# reaction-game.net
KiCad netlist of a schematic drawn in EasyEDA
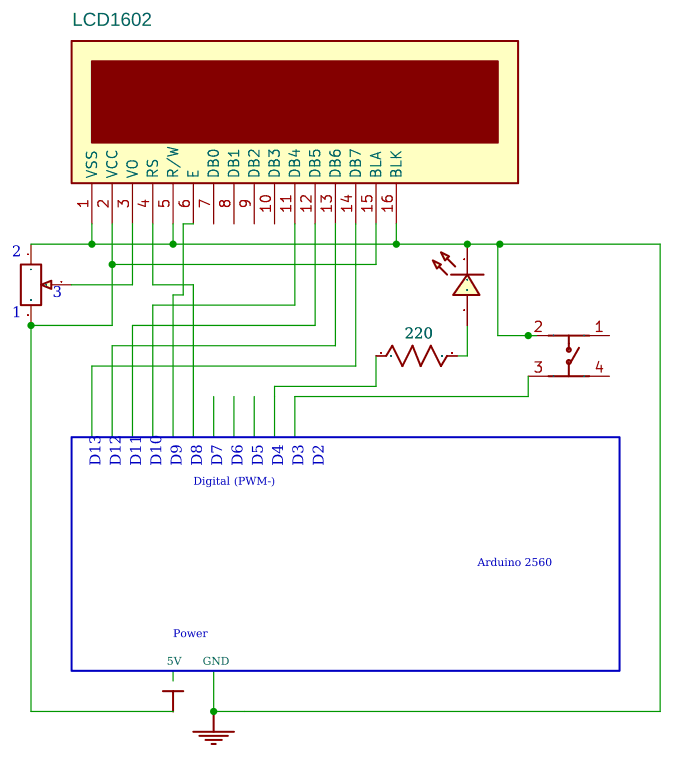
[diagram p0: schematic sheet]

(export (version "E")
  (design (tool "Eeschema 10.0.6"))
  (components
    (comp (ref "KEY1")
      (value "button6*6*8")
      (fields (field (name "BOM_Supplier Part") "C59982"))
      (libsource (lib "") (part "button6*6*8"))
    )
    (comp (ref "LCD1")
      (value "LCD1602")
      (fields
        (field (name "BOM_Manufacturer Part") "LCM1602K-NSW-BBW")
        (field (name "BOM_Supplier Part") "C83275")
      )
      (libsource (lib "") (part "LCD1602"))
    )
    (comp (ref "LED1")
      (value "LED-0603_R")
      (fields
        (field (name "BOM_Manufacturer Part") "19-217/R6C-AL1M2VY/3T")
        (field (name "BOM_Supplier Part") "C72044")
      )
      (libsource (lib "") (part "LED-0603_R"))
    )
    (comp (ref "R1") (value "220") (libsource (lib "") (part "R_0603_US")))
    (comp (ref "RP1") (value "R_3386P_EU") (libsource (lib "") (part "R_3386P_EU")))
  )
  (nets
    (net (code "1") (name "5V") (class "Default")
      (node (ref "LCD1") (pin "15") (pinfunction "BLA_15") (pintype "unspecified"))
      (node (ref "LCD1") (pin "2") (pinfunction "VCC_2") (pintype "unspecified"))
      (node (ref "RP1") (pin "3") (pinfunction "3_3") (pintype "input"))
    )
    (net (code "2") (name "GND") (class "Default")
      (node (ref "KEY1") (pin "2") (pinfunction "2_2") (pintype "unspecified"))
      (node (ref "LCD1") (pin "1") (pinfunction "VSS_1") (pintype "unspecified"))
      (node (ref "LCD1") (pin "16") (pinfunction "BLK_16") (pintype "unspecified"))
      (node (ref "LCD1") (pin "5") (pinfunction "R/W_5") (pintype "unspecified"))
      (node (ref "LED1") (pin "2") (pinfunction "2_2") (pintype "unspecified"))
      (node (ref "RP1") (pin "1") (pinfunction "1_1") (pintype "input"))
    )
    (net (code "3") (name "Net-(LCD1-VO)") (class "Default")
      (node (ref "LCD1") (pin "3") (pinfunction "VO_3") (pintype "unspecified"))
      (node (ref "RP1") (pin "2") (pinfunction "2_2") (pintype "input"))
    )
    (net (code "4") (name "Net-(LED1-Pad1)") (class "Default")
      (node (ref "LED1") (pin "1") (pinfunction "1_1") (pintype "unspecified"))
      (node (ref "R1") (pin "2") (pinfunction "2_2") (pintype "unspecified"))
    )
    (net (code "5") (name "unconnected-(KEY1-Pad1)") (class "Default")
      (node (ref "KEY1") (pin "1") (pinfunction "1_1") (pintype "unspecified"))
    )
    (net (code "6") (name "unconnected-(KEY1-Pad3)") (class "Default")
      (node (ref "KEY1") (pin "3") (pinfunction "3_3") (pintype "unspecified"))
    )
    (net (code "7") (name "unconnected-(KEY1-Pad4)") (class "Default")
      (node (ref "KEY1") (pin "4") (pinfunction "4_4") (pintype "unspecified"))
    )
    (net (code "8") (name "unconnected-(LCD1-DB0-Pad7)") (class "Default")
      (node (ref "LCD1") (pin "7") (pinfunction "DB0_7") (pintype "unspecified"))
    )
    (net (code "9") (name "unconnected-(LCD1-DB1-Pad8)") (class "Default")
      (node (ref "LCD1") (pin "8") (pinfunction "DB1_8") (pintype "unspecified"))
    )
    (net (code "10") (name "unconnected-(LCD1-DB2-Pad9)") (class "Default")
      (node (ref "LCD1") (pin "9") (pinfunction "DB2_9") (pintype "unspecified"))
    )
    (net (code "11") (name "unconnected-(LCD1-DB3-Pad10)") (class "Default")
      (node (ref "LCD1") (pin "10") (pinfunction "DB3_10") (pintype "unspecified"))
    )
    (net (code "12") (name "unconnected-(LCD1-DB4-Pad11)") (class "Default")
      (node (ref "LCD1") (pin "11") (pinfunction "DB4_11") (pintype "unspecified"))
    )
    (net (code "13") (name "unconnected-(LCD1-DB5-Pad12)") (class "Default")
      (node (ref "LCD1") (pin "12") (pinfunction "DB5_12") (pintype "unspecified"))
    )
    (net (code "14") (name "unconnected-(LCD1-DB6-Pad13)") (class "Default")
      (node (ref "LCD1") (pin "13") (pinfunction "DB6_13") (pintype "unspecified"))
    )
    (net (code "15") (name "unconnected-(LCD1-DB7-Pad14)") (class "Default")
      (node (ref "LCD1") (pin "14") (pinfunction "DB7_14") (pintype "unspecified"))
    )
    (net (code "16") (name "unconnected-(LCD1-E-Pad6)") (class "Default")
      (node (ref "LCD1") (pin "6") (pinfunction "E_6") (pintype "unspecified"))
    )
    (net (code "17") (name "unconnected-(LCD1-RS-Pad4)") (class "Default")
      (node (ref "LCD1") (pin "4") (pinfunction "RS_4") (pintype "unspecified"))
    )
    (net (code "18") (name "unconnected-(R1-Pad1)") (class "Default")
      (node (ref "R1") (pin "1") (pinfunction "1_1") (pintype "unspecified"))
    )
  )
)
